# ads1231.net
KiCad netlist of a schematic drawn in EAGLE
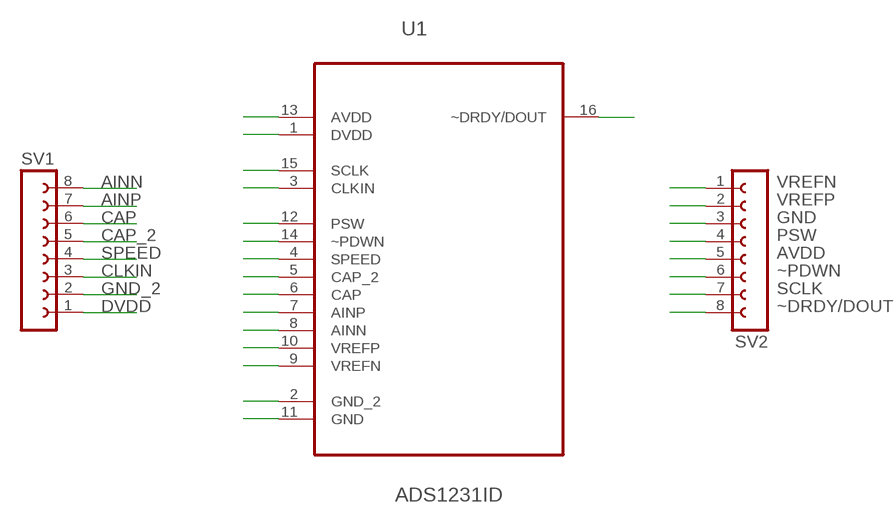
[diagram p0: schematic, sheet 1]

(export (version "E")
  (design (tool "Eeschema 10.0.6"))
  (components
    (comp (ref "SV1")
      (value "FE08-1")
      (footprint "eagle-import:FE08")
      (libsource (lib "eagle-import") (part "FE08-1"))
    )
    (comp (ref "SV2")
      (value "FE08-1")
      (footprint "eagle-import:FE08")
      (libsource (lib "eagle-import") (part "FE08-1"))
    )
    (comp (ref "U1")
      (value "ADS1231ID")
      (footprint "eagle-import:SOIC127P600X175-16N")
      (libsource (lib "eagle-import") (part "ADS1231ID"))
    )
  )
  (nets
    (net (code "1") (name "/AINN") (class "Default")
      (node (ref "SV1") (pin "8") (pinfunction "8_8") (pintype "passive"))
      (node (ref "U1") (pin "8") (pinfunction "AINN_8") (pintype "input"))
    )
    (net (code "2") (name "/AINP") (class "Default")
      (node (ref "SV1") (pin "7") (pinfunction "7_7") (pintype "passive"))
      (node (ref "U1") (pin "7") (pinfunction "AINP_7") (pintype "input"))
    )
    (net (code "3") (name "/AVDD") (class "Default")
      (node (ref "SV2") (pin "5") (pinfunction "5_5") (pintype "passive"))
      (node (ref "U1") (pin "13") (pinfunction "AVDD_13") (pintype "power_in"))
    )
    (net (code "4") (name "/CAP") (class "Default")
      (node (ref "SV1") (pin "6") (pinfunction "6_6") (pintype "passive"))
      (node (ref "U1") (pin "6") (pinfunction "CAP_6") (pintype "input"))
    )
    (net (code "5") (name "/CAP_2") (class "Default")
      (node (ref "SV1") (pin "5") (pinfunction "5_5") (pintype "passive"))
      (node (ref "U1") (pin "5") (pinfunction "CAP_2_5") (pintype "input"))
    )
    (net (code "6") (name "/CLKIN") (class "Default")
      (node (ref "SV1") (pin "3") (pinfunction "3_3") (pintype "passive"))
      (node (ref "U1") (pin "3") (pinfunction "CLKIN_3") (pintype "input"))
    )
    (net (code "7") (name "/DVDD") (class "Default")
      (node (ref "SV1") (pin "1") (pinfunction "1_1") (pintype "passive"))
      (node (ref "U1") (pin "1") (pinfunction "DVDD_1") (pintype "power_in"))
    )
    (net (code "8") (name "/GND") (class "Default")
      (node (ref "SV2") (pin "3") (pinfunction "3_3") (pintype "passive"))
      (node (ref "U1") (pin "11") (pinfunction "GND_11") (pintype "passive"))
    )
    (net (code "9") (name "/GND_2") (class "Default")
      (node (ref "SV1") (pin "2") (pinfunction "2_2") (pintype "passive"))
      (node (ref "U1") (pin "2") (pinfunction "GND_2_2") (pintype "passive"))
    )
    (net (code "10") (name "/PSW") (class "Default")
      (node (ref "SV2") (pin "4") (pinfunction "4_4") (pintype "passive"))
      (node (ref "U1") (pin "12") (pinfunction "PSW_12") (pintype "input"))
    )
    (net (code "11") (name "/SCLK") (class "Default")
      (node (ref "SV2") (pin "7") (pinfunction "7_7") (pintype "passive"))
      (node (ref "U1") (pin "15") (pinfunction "SCLK_15") (pintype "input"))
    )
    (net (code "12") (name "/SPEED") (class "Default")
      (node (ref "SV1") (pin "4") (pinfunction "4_4") (pintype "passive"))
      (node (ref "U1") (pin "4") (pinfunction "SPEED_4") (pintype "input"))
    )
    (net (code "13") (name "/VREFN") (class "Default")
      (node (ref "SV2") (pin "1") (pinfunction "1_1") (pintype "passive"))
      (node (ref "U1") (pin "9") (pinfunction "VREFN_9") (pintype "input"))
    )
    (net (code "14") (name "/VREFP") (class "Default")
      (node (ref "SV2") (pin "2") (pinfunction "2_2") (pintype "passive"))
      (node (ref "U1") (pin "10") (pinfunction "VREFP_10") (pintype "input"))
    )
    (net (code "15") (name "/~{DRDY{slash}DOUT}") (class "Default")
      (node (ref "SV2") (pin "8") (pinfunction "8_8") (pintype "passive"))
      (node (ref "U1") (pin "16") (pinfunction "~{DRDY/DOUT}_16") (pintype "output"))
    )
    (net (code "16") (name "/~{PDWN}") (class "Default")
      (node (ref "SV2") (pin "6") (pinfunction "6_6") (pintype "passive"))
      (node (ref "U1") (pin "14") (pinfunction "~{PDWN}_14") (pintype "input"))
    )
  )
)
